# panel.net
KiCad netlist of a schematic drawn in EAGLE
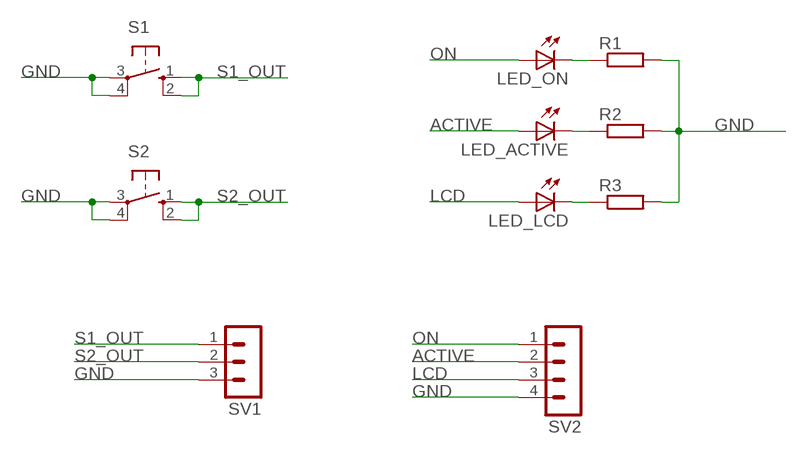
[diagram p0: schematic, sheet 1]

(export (version "E")
  (design (tool "Eeschema 10.0.6"))
  (components
    (comp (ref "LED_ACTIVE")
      (value "LED_ELD260")
      (footprint "eagle-import:LED_LD260")
      (libsource (lib "eagle-import") (part "LED_ELD260"))
    )
    (comp (ref "LED_LCD")
      (value "LED_ELD260")
      (footprint "eagle-import:LED_LD260")
      (libsource (lib "eagle-import") (part "LED_ELD260"))
    )
    (comp (ref "LED_ON")
      (value "LED_ELD260")
      (footprint "eagle-import:LED_LD260")
      (libsource (lib "eagle-import") (part "LED_ELD260"))
    )
    (comp (ref "R1")
      (value "R-EU_R1206")
      (footprint "eagle-import:R1206")
      (libsource (lib "eagle-import") (part "R-EU_R1206"))
    )
    (comp (ref "R2")
      (value "R-EU_R1206")
      (footprint "eagle-import:R1206")
      (libsource (lib "eagle-import") (part "R-EU_R1206"))
    )
    (comp (ref "R3")
      (value "R-EU_R1206")
      (footprint "eagle-import:R1206")
      (libsource (lib "eagle-import") (part "R-EU_R1206"))
    )
    (comp (ref "S1")
      (value "10-XX")
      (footprint "eagle-import:B3F-10XX")
      (fields (field (name "MPN") "B3F-1000"))
      (libsource (lib "eagle-import") (part "10-XX"))
    )
    (comp (ref "S2")
      (value "10-XX")
      (footprint "eagle-import:B3F-10XX")
      (fields (field (name "MPN") "B3F-1000"))
      (libsource (lib "eagle-import") (part "10-XX"))
    )
    (comp (ref "SV1")
      (value "MA03-1")
      (footprint "eagle-import:MA03-1")
      (libsource (lib "eagle-import") (part "MA03-1"))
    )
    (comp (ref "SV2")
      (value "MA04-1")
      (footprint "eagle-import:MA04-1")
      (libsource (lib "eagle-import") (part "MA04-1"))
    )
  )
  (nets
    (net (code "1") (name "/ACTIVE") (class "Default")
      (node (ref "LED_ACTIVE") (pin "A") (pinfunction "A_A") (pintype "passive"))
      (node (ref "SV2") (pin "2") (pinfunction "2_2") (pintype "passive"))
    )
    (net (code "2") (name "/GND") (class "Default")
      (node (ref "R1") (pin "2") (pinfunction "2_2") (pintype "passive"))
      (node (ref "R2") (pin "2") (pinfunction "2_2") (pintype "passive"))
      (node (ref "R3") (pin "2") (pinfunction "2_2") (pintype "passive"))
      (node (ref "S1") (pin "3") (pinfunction "P_3") (pintype "passive"))
      (node (ref "S1") (pin "4") (pinfunction "P1_4") (pintype "passive"))
      (node (ref "S2") (pin "3") (pinfunction "P_3") (pintype "passive"))
      (node (ref "S2") (pin "4") (pinfunction "P1_4") (pintype "passive"))
      (node (ref "SV1") (pin "3") (pinfunction "3_3") (pintype "passive"))
      (node (ref "SV2") (pin "4") (pinfunction "4_4") (pintype "passive"))
    )
    (net (code "3") (name "/LCD") (class "Default")
      (node (ref "LED_LCD") (pin "A") (pinfunction "A_A") (pintype "passive"))
      (node (ref "SV2") (pin "3") (pinfunction "3_3") (pintype "passive"))
    )
    (net (code "4") (name "/ON") (class "Default")
      (node (ref "LED_ON") (pin "A") (pinfunction "A_A") (pintype "passive"))
      (node (ref "SV2") (pin "1") (pinfunction "1_1") (pintype "passive"))
    )
    (net (code "5") (name "/S1_OUT") (class "Default")
      (node (ref "S1") (pin "1") (pinfunction "S_1") (pintype "passive"))
      (node (ref "S1") (pin "2") (pinfunction "S1_2") (pintype "passive"))
      (node (ref "SV1") (pin "1") (pinfunction "1_1") (pintype "passive"))
    )
    (net (code "6") (name "/S2_OUT") (class "Default")
      (node (ref "S2") (pin "1") (pinfunction "S_1") (pintype "passive"))
      (node (ref "S2") (pin "2") (pinfunction "S1_2") (pintype "passive"))
      (node (ref "SV1") (pin "2") (pinfunction "2_2") (pintype "passive"))
    )
    (net (code "7") (name "Net-(LED_ACTIVE-C)") (class "Default")
      (node (ref "LED_ACTIVE") (pin "K") (pinfunction "C_K") (pintype "passive"))
      (node (ref "R2") (pin "1") (pinfunction "1_1") (pintype "passive"))
    )
    (net (code "8") (name "Net-(LED_LCD-C)") (class "Default")
      (node (ref "LED_LCD") (pin "K") (pinfunction "C_K") (pintype "passive"))
      (node (ref "R3") (pin "1") (pinfunction "1_1") (pintype "passive"))
    )
    (net (code "9") (name "Net-(LED_ON-C)") (class "Default")
      (node (ref "LED_ON") (pin "K") (pinfunction "C_K") (pintype "passive"))
      (node (ref "R1") (pin "1") (pinfunction "1_1") (pintype "passive"))
    )
  )
)
